# Power_Section.net
KiCad netlist of a schematic drawn in Altium Designer
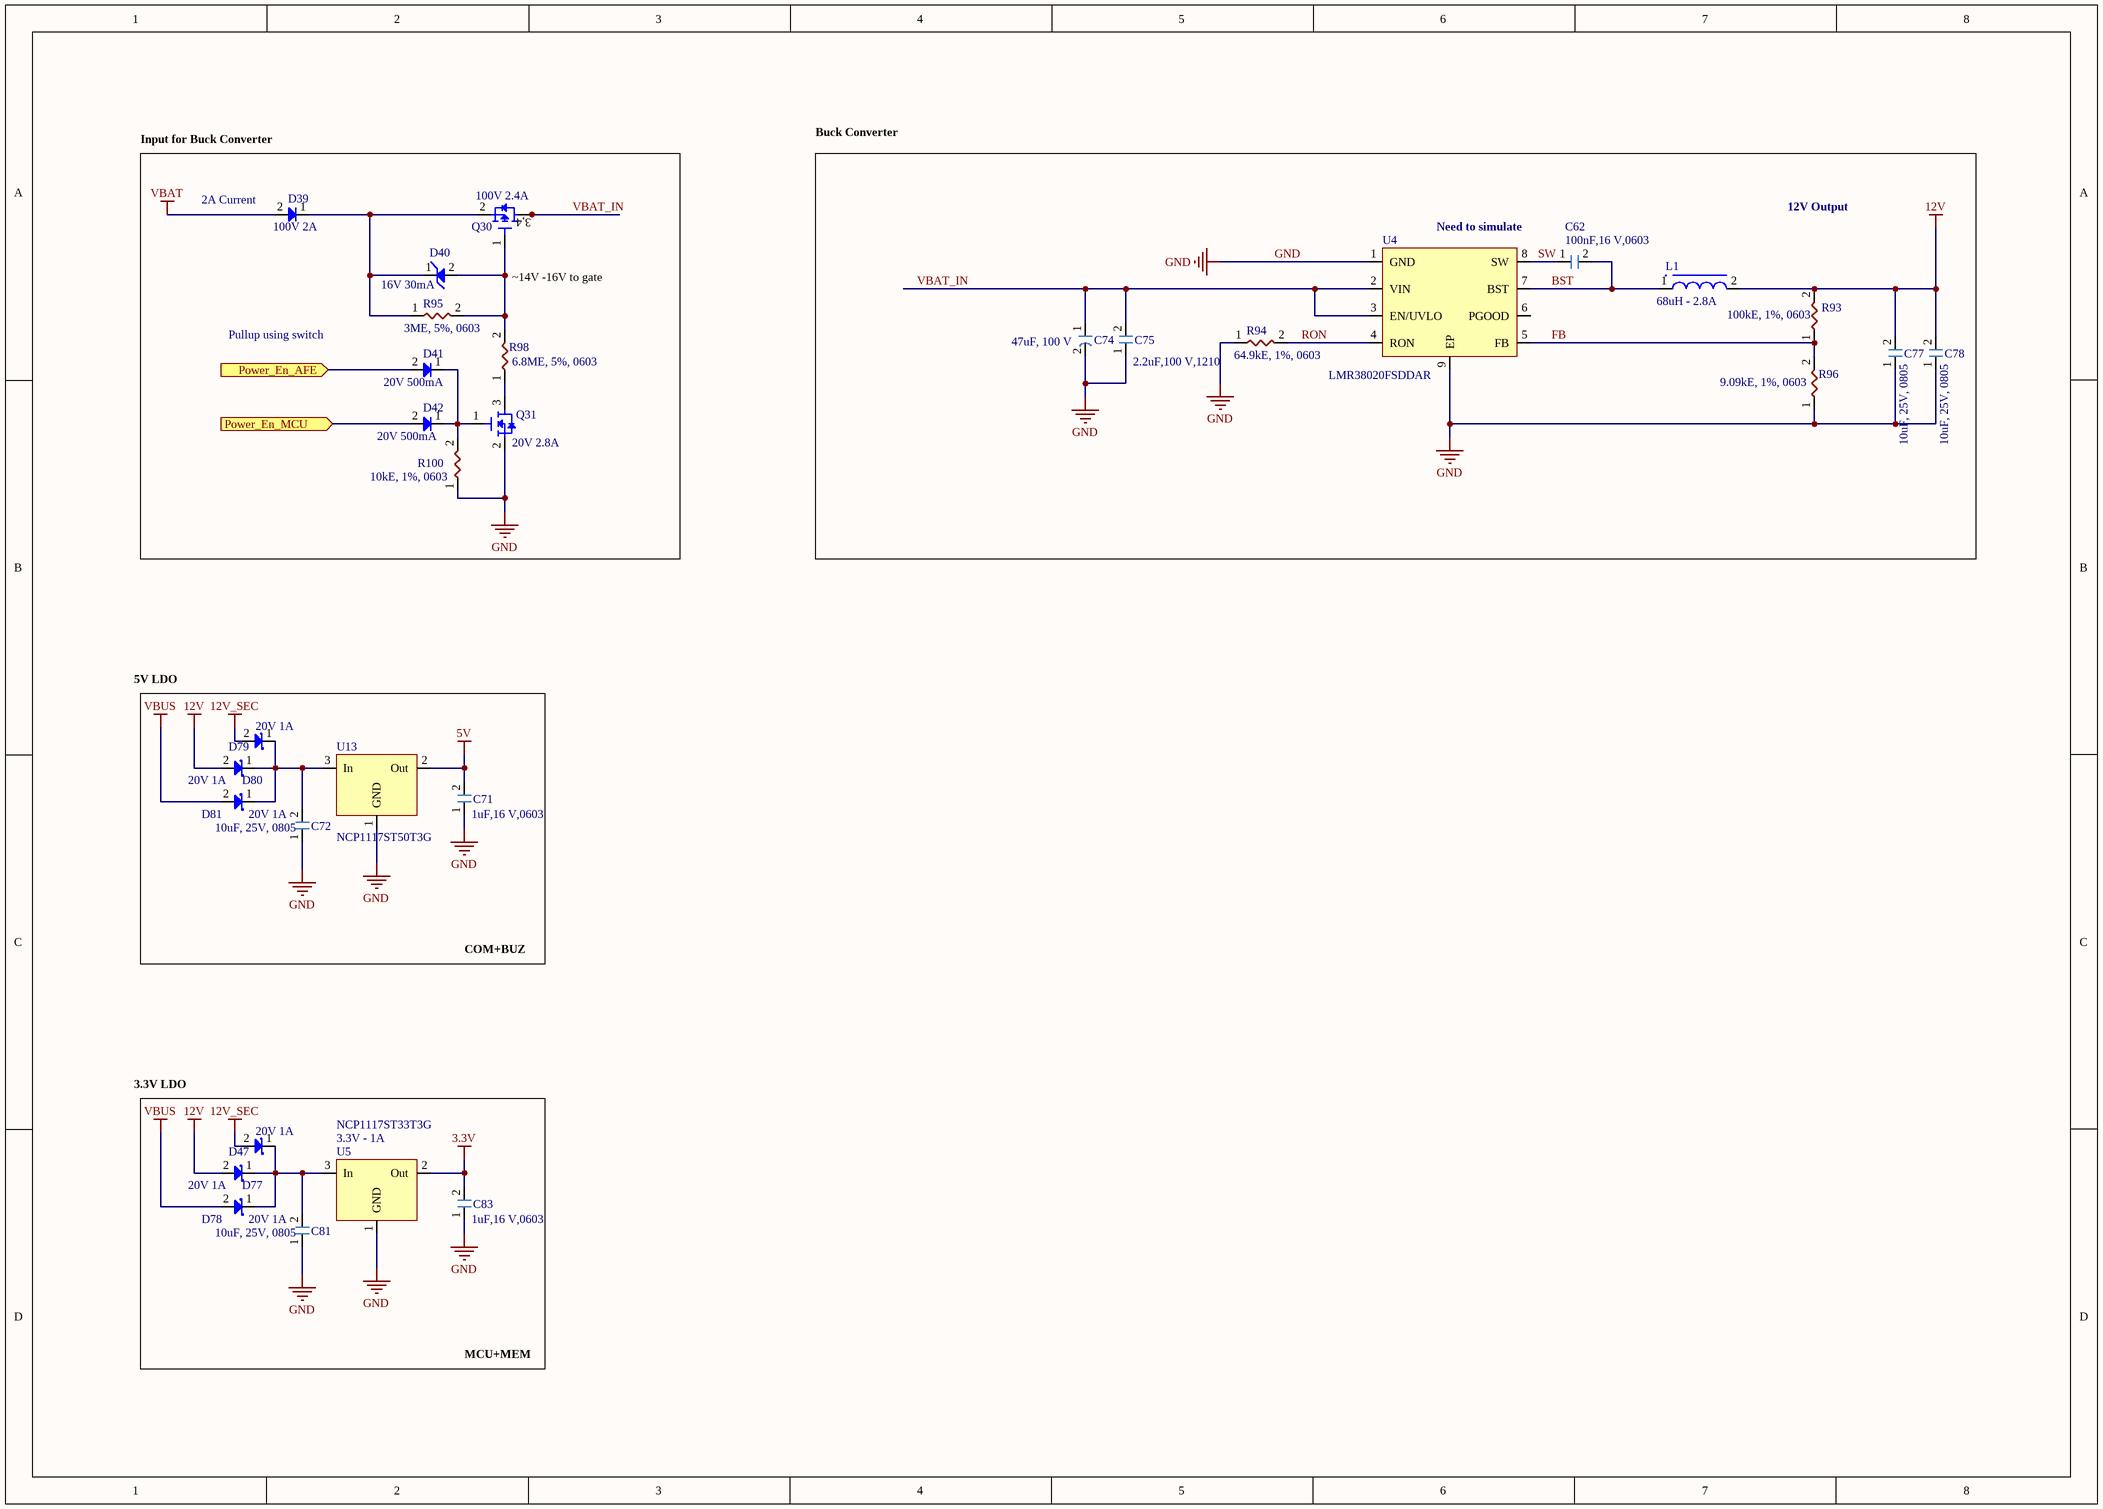
[diagram p0: Power Section.SchDoc]

(export (version "E")
  (design (tool "Eeschema 10.0.6"))
  (components
    (comp (ref "C62")
      (value "CC0603KRX7R7BB104")
      (footprint "BMS_V2.1_Adv:CAPC1608X05N 0603")
      (description "Multilayer Ceramic Capacitor, 100 nF, 16V, ±10%,  X7R 0603 [1608 Metric]")
      (fields
        (field (name "MANUFACTURER") "Yageo")
        (field (name "TOLERANCE") "10%")
        (field (name "VALUE DISPLAY") "100nF,16 V,0603")
      )
      (libsource (lib "BMS_V2.1_Adv") (part "Cap_CC0603KRX7R7BB104"))
    )
    (comp (ref "C71")
      (value "CGA3E1X7R1C105K080AC")
      (footprint "CAPC1608X05N 0603")
      (description "Multilayer Ceramic Capacitor, 1uF, 16V, ±10%,  X7R 0603 [1608 Metric]")
      (fields
        (field (name "MANUFACTURER") "TDK Corporation")
        (field (name "VOLTAGE") "16V")
        (field (name "VALUE DISPLAY") "1uF,16 V,0603")
      )
      (libsource (lib "BMS_V2.1_Adv") (part "Cap_CGA3E1X7R1C105K080AC"))
    )
    (comp (ref "C72")
      (value "GRM21BZ71E106KE15L")
      (footprint "BMS_V2.1_Adv:CAPC2012X13N 0805")
      (description "Multilayer Ceramic Capacitor, 10 uF, 25V, ±10%,  X7R 0805 (2012 Metric)")
      (fields
        (field (name "MANUFACTURER") "Murata")
        (field (name "TOLERANCE") "10%")
        (field (name "VALUE DISPLAY") "10uF, 25V, 0805")
      )
      (libsource (lib "BMS_V2.1_Adv") (part "Cap_GRM21BZ71E106KE15L"))
    )
    (comp (ref "C74")
      (value "ESW476M100AH2AA")
      (footprint "Aluminium Electrolytic Capacitor")
      (description "Aluminum Electrolytic Capacitors Radial, 47 µF 100 V, Can 370mOhm @ 100kHz 5000 Hrs @ 105°C")
      (fields
        (field (name "MANUFACTURER") "KEMET")
        (field (name "TOLERANCE") "20%")
        (field (name "VALUE DISPLAY") "47uF, 100 V")
      )
      (libsource (lib "BMS_V2.1_Adv") (part "Cap_ESW476M100AH2AA"))
    )
    (comp (ref "C75")
      (value "HMK325B7225KMHT")
      (footprint "CAPC3225X28N 1210")
      (description "Multilayer Ceramic Capacitor, 2.2 uF, 100 V, ± 10%, X7R, 1210 [3225 Metric]")
      (fields
        (field (name "MANUFACTURER") "Taiyo Yuden")
        (field (name "TOLERANCE") "10%")
        (field (name "VALUE DISPLAY") "2.2uF,100 V,1210")
      )
      (libsource (lib "BMS_V2.1_Adv") (part "Cap_HMK325B7225KMHT"))
    )
    (comp (ref "C77")
      (value "GRM21BZ71E106KE15L")
      (footprint "BMS_V2.1_Adv:CAPC2012X13N 0805")
      (description "Multilayer Ceramic Capacitor, 10 uF, 25V, ±10%,  X7R 0805 (2012 Metric)")
      (fields
        (field (name "MANUFACTURER") "Murata")
        (field (name "TOLERANCE") "10%")
        (field (name "VALUE DISPLAY") "10uF, 25V, 0805")
      )
      (libsource (lib "BMS_V2.1_Adv") (part "Cap_GRM21BZ71E106KE15L"))
    )
    (comp (ref "C78")
      (value "GRM21BZ71E106KE15L")
      (footprint "BMS_V2.1_Adv:CAPC2012X13N 0805")
      (description "Multilayer Ceramic Capacitor, 10 uF, 25V, ±10%,  X7R 0805 (2012 Metric)")
      (fields
        (field (name "MANUFACTURER") "Murata")
        (field (name "TOLERANCE") "10%")
        (field (name "VALUE DISPLAY") "10uF, 25V, 0805")
      )
      (libsource (lib "BMS_V2.1_Adv") (part "Cap_GRM21BZ71E106KE15L"))
    )
    (comp (ref "C81")
      (value "GRM21BZ71E106KE15L")
      (footprint "BMS_V2.1_Adv:CAPC2012X13N 0805")
      (description "Multilayer Ceramic Capacitor, 10 uF, 25V, ±10%,  X7R 0805 (2012 Metric)")
      (fields
        (field (name "MANUFACTURER") "Murata")
        (field (name "TOLERANCE") "10%")
        (field (name "VALUE DISPLAY") "10uF, 25V, 0805")
      )
      (libsource (lib "BMS_V2.1_Adv") (part "Cap_GRM21BZ71E106KE15L"))
    )
    (comp (ref "C83")
      (value "CGA3E1X7R1C105K080AC")
      (footprint "CAPC1608X05N 0603")
      (description "Multilayer Ceramic Capacitor, 1uF, 16V, ±10%,  X7R 0603 [1608 Metric]")
      (fields
        (field (name "MANUFACTURER") "TDK Corporation")
        (field (name "VOLTAGE") "16V")
        (field (name "VALUE DISPLAY") "1uF,16 V,0603")
      )
      (libsource (lib "BMS_V2.1_Adv") (part "Cap_CGA3E1X7R1C105K080AC"))
    )
    (comp (ref "D39")
      (value "STPS2H100ZFY")
      (footprint "SODFL350X110-2N")
      (description "Diode 100 V 2A Surface Mount SOD-123F")
      (fields
        (field (name "MANUFACTURER") "ST")
        (field (name "VALUE DISPLAY") "100V 2A")
        (field (name "VOLTAGE") "100V")
      )
      (libsource (lib "BMS_V2.1_Adv") (part "Diode_STPS2H100ZFY"))
    )
    (comp (ref "D40")
      (value "MMSZ5246BQ-7-F")
      (footprint "DIODE_SOD123")
      (description "Zener Diode 16 V 500 mW ±5% Surface Mount SOD-123")
      (fields
        (field (name "MANUFACTURER") "Diodes Inc.")
        (field (name "POWER") "370mW")
        (field (name "VALUE DISPLAY") "16V 30mA")
      )
      (libsource (lib "BMS_V2.1_Adv") (part "Diode_MMSZ5246BQ-7-F"))
    )
    (comp (ref "D41")
      (value "SBR80520LT1G")
      (footprint "DIODE_SOD123")
      (description "Diode 20 V 500mA Surface Mount SOD-123")
      (fields
        (field (name "MANUFACTURER") "OnSemi")
        (field (name "VALUE DISPLAY") "20V 500mA")
        (field (name "VOLTAGE") "20V")
      )
      (libsource (lib "BMS_V2.1_Adv") (part "Diode_SBR80520LT1G"))
    )
    (comp (ref "D42")
      (value "SBR80520LT1G")
      (footprint "DIODE_SOD123")
      (description "Diode 20 V 500mA Surface Mount SOD-123")
      (fields
        (field (name "MANUFACTURER") "OnSemi")
        (field (name "VALUE DISPLAY") "20V 500mA")
        (field (name "VOLTAGE") "20V")
      )
      (libsource (lib "BMS_V2.1_Adv") (part "Diode_SBR80520LT1G"))
    )
    (comp (ref "D47")
      (value "MBR120LSFT3G")
      (footprint "BMS_V2.1_Adv:SODFL360X98-2N")
      (description "DIODE SCHOTTKY 20V 1A SOD123FL")
      (fields
        (field (name "MANUFACTURER") "OnSemi")
        (field (name "VALUE DISPLAY") "20V 1A")
        (field (name "VOLTAGE") "20V")
      )
      (libsource (lib "BMS_V2.1_Adv") (part "Diode_MBR120LSFT3G"))
    )
    (comp (ref "D77")
      (value "MBR120LSFT3G")
      (footprint "BMS_V2.1_Adv:SODFL360X98-2N")
      (description "DIODE SCHOTTKY 20V 1A SOD123FL")
      (fields
        (field (name "MANUFACTURER") "OnSemi")
        (field (name "VALUE DISPLAY") "20V 1A")
        (field (name "VOLTAGE") "20V")
      )
      (libsource (lib "BMS_V2.1_Adv") (part "Diode_MBR120LSFT3G"))
    )
    (comp (ref "D78")
      (value "MBR120LSFT3G")
      (footprint "BMS_V2.1_Adv:SODFL360X98-2N")
      (description "DIODE SCHOTTKY 20V 1A SOD123FL")
      (fields
        (field (name "MANUFACTURER") "OnSemi")
        (field (name "VALUE DISPLAY") "20V 1A")
        (field (name "VOLTAGE") "20V")
      )
      (libsource (lib "BMS_V2.1_Adv") (part "Diode_MBR120LSFT3G"))
    )
    (comp (ref "D79")
      (value "MBR120LSFT3G")
      (footprint "BMS_V2.1_Adv:SODFL360X98-2N")
      (description "DIODE SCHOTTKY 20V 1A SOD123FL")
      (fields
        (field (name "MANUFACTURER") "OnSemi")
        (field (name "VALUE DISPLAY") "20V 1A")
        (field (name "VOLTAGE") "20V")
      )
      (libsource (lib "BMS_V2.1_Adv") (part "Diode_MBR120LSFT3G"))
    )
    (comp (ref "D80")
      (value "MBR120LSFT3G")
      (footprint "BMS_V2.1_Adv:SODFL360X98-2N")
      (description "DIODE SCHOTTKY 20V 1A SOD123FL")
      (fields
        (field (name "MANUFACTURER") "OnSemi")
        (field (name "VALUE DISPLAY") "20V 1A")
        (field (name "VOLTAGE") "20V")
      )
      (libsource (lib "BMS_V2.1_Adv") (part "Diode_MBR120LSFT3G"))
    )
    (comp (ref "D81")
      (value "MBR120LSFT3G")
      (footprint "BMS_V2.1_Adv:SODFL360X98-2N")
      (description "DIODE SCHOTTKY 20V 1A SOD123FL")
      (fields
        (field (name "MANUFACTURER") "OnSemi")
        (field (name "VALUE DISPLAY") "20V 1A")
        (field (name "VOLTAGE") "20V")
      )
      (libsource (lib "BMS_V2.1_Adv") (part "Diode_MBR120LSFT3G"))
    )
    (comp (ref "L1")
      (value "MSS1210-683ME")
      (footprint "BMS_V2.1_Adv:INDP120120X102N")
      (description "68 µH Shielded Drum Core, Wirewound Inductor 2.8 A 80mOhm Max Nonstandard")
      (fields
        (field (name "MANUFACTURER") "Coilcraft")
        (field (name "MANUFACTURER PART NUMBER") "MSS1210-683MED")
        (field (name "VALUE DISPLAY") "68uH - 2.8A")
      )
      (libsource (lib "BMS_V2.1_Adv") (part "Ind_MSS1210-683ME"))
    )
    (comp (ref "Q30")
      (value "ZXMP10A17GQTA")
      (footprint "SOT230P700X180-4N")
      (description "P-Channel 100 V 2.4A (Ta) 2W (Ta) Surface Mount SOT-223-3")
      (fields
        (field (name "MANUFACTURER") "Diodes Inc.")
        (field (name "POWER") "2W")
        (field (name "VALUE DISPLAY") "100V 2.4A")
      )
      (libsource (lib "BMS_V2.1_Adv") (part "FET_ZXMP10A17GQTA"))
    )
    (comp (ref "Q31")
      (value "DMG2302UK-7")
      (footprint "BMS_V2.1_Adv:SOT95P255X140-3N")
      (description "N-Channel 20 V 2.8A (Ta) 660mW (Ta) Surface Mount SOT-23-3")
      (fields
        (field (name "MANUFACTURER") "Diodes Inc.")
        (field (name "POWER") "660mW")
        (field (name "VALUE DISPLAY") "20V 2.8A")
      )
      (libsource (lib "BMS_V2.1_Adv") (part "FET_DMG2302UK-7"))
    )
    (comp (ref "R93")
      (value "CRCW0805100KFKEA")
      (footprint "BMS_V2.1_Adv:RESC1608X05N 0603")
      (description "SMD Chip Resistor, 100k Ohm, ± 1%, 100 mW, 0603 [1608 Metric], Thick Film, General Purpose")
      (fields
        (field (name "MANUFACTURER") "Vishay Dale")
        (field (name "MANUFACTURER PART NUMBER") "CRCW0603100KFKEA")
        (field (name "VALUE DISPLAY") "100kE, 1%, 0603")
      )
      (libsource (lib "BMS_V2.1_Adv") (part "Res_CRCW0603100KFKEA"))
    )
    (comp (ref "R94")
      (value "AC0603FR-0764K9L")
      (footprint "BMS_V2.1_Adv:RESC1608X05N 0603")
      (fields
        (field (name "MANUFACTURER") "Yageo")
        (field (name "POWER") "1/10W")
        (field (name "TOLERANCE") "1%")
        (field (name "VALUE DISPLAY") "64.9kE, 1%, 0603")
      )
      (libsource (lib "BMS_V2.1_Adv") (part "Res_AC0603FR-0764K9L"))
    )
    (comp (ref "R95")
      (value "CRCW06033M00JNEA")
      (footprint "RESC1608X05N 0603")
      (fields
        (field (name "MANUFACTURER") "Vishay Dale")
        (field (name "POWER") "1/10W")
        (field (name "TOLERANCE") "5%")
        (field (name "VALUE DISPLAY") "3ME, 5%, 0603")
      )
      (libsource (lib "BMS_V2.1_Adv") (part "Res_CRCW06033M00JNEA"))
    )
    (comp (ref "R96")
      (value "AC0603FR-079K09L")
      (footprint "BMS_V2.1_Adv:RESC1608X05N 0603")
      (fields
        (field (name "MANUFACTURER") "Yageo")
        (field (name "POWER") "1/10W")
        (field (name "TOLERANCE") "1%")
        (field (name "VALUE DISPLAY") "9.09kE, 1%, 0603")
      )
      (libsource (lib "BMS_V2.1_Adv") (part "Res_AC0603FR-079K09L"))
    )
    (comp (ref "R98")
      (value "CRCW06036M80JNEA")
      (footprint "RESC1608X05N 0603")
      (fields
        (field (name "MANUFACTURER") "Vishay Dale")
        (field (name "POWER") "1/10W")
        (field (name "TOLERANCE") "5%")
        (field (name "VALUE DISPLAY") "6.8ME, 5%, 0603")
      )
      (libsource (lib "BMS_V2.1_Adv") (part "Res_CRCW06036M80JNEA"))
    )
    (comp (ref "R100")
      (value "CRCW060310K0FKEA")
      (footprint "RESC1608X05N 0603")
      (description "SMD Chip Resistor, 10 kOhm,±1%, 100 mW, 0603 [1608 Metric], Thick Film, General Purpose")
      (fields
        (field (name "MANUFACTURER") "Vishay Dale")
        (field (name "POWER") "1/10W")
        (field (name "VALUE DISPLAY") "10kE, 1%, 0603")
      )
      (libsource (lib "BMS_V2.1_Adv") (part "Res_CRCW060310K0FKEA"))
    )
    (comp (ref "U4")
      (value "LMR38020FSDDAR")
      (footprint "BMS_V2.1_Adv:SOIC127P600X170_HS-9N LM5164")
      (description "Buck Switching Regulator IC Positive Adjustable 1V 1 Output 2A 8-PowerSOIC (0.154\", 3.90mm Width)")
      (fields (field (name "MANUFACTURER") "Texas Instruments") (field (name "VOLTAGE") "4.5V - 80V"))
      (libsource (lib "BMS_V2.1_Adv") (part "IC_LMR38020FSDDAR"))
    )
    (comp (ref "U5")
      (value "NCP1117ST33T3G")
      (footprint "BMS_V2.1_Adv:SOT230P700X180-4N - NCP")
      (description "LDO Voltage Regulators 3.3V 1A Positive")
      (fields
        (field (name "MANUFACTURER") "OnSemi")
        (field (name "VALUE DISPLAY") "3.3V - 1A")
        (field (name "VOLTAGE") "20V (Max)")
      )
      (libsource (lib "BMS_V2.1_Adv") (part "IC_NCP1117ST33T3G"))
    )
    (comp (ref "U13")
      (value "NCP1117ST50T3G")
      (footprint "BMS_V2.1_Adv:SOT230P700X180-4N - NCP")
      (description "LDO Voltage Regulators 5V 1A Positive")
      (fields (field (name "MANUFACTURER") "OnSemi") (field (name "VOLTAGE") "20V (Max)"))
      (libsource (lib "BMS_V2.1_Adv") (part "IC_NCP1117ST50T3G"))
    )
  )
  (nets
    (net (code "1") (name "/BST") (class "Default")
      (node (ref "C62") (pin "2") (pinfunction "2_2") (pintype "passive"))
      (node (ref "L1") (pin "1") (pinfunction "1_1") (pintype "passive"))
      (node (ref "U4") (pin "7") (pinfunction "BST_7") (pintype "passive"))
    )
    (net (code "2") (name "/FB") (class "Default")
      (node (ref "R93") (pin "1") (pinfunction "1_1") (pintype "passive"))
      (node (ref "R96") (pin "2") (pinfunction "2_2") (pintype "passive"))
      (node (ref "U4") (pin "5") (pinfunction "FB_5") (pintype "passive"))
    )
    (net (code "3") (name "/Power_En_AFE") (class "Default")
      (node (ref "D41") (pin "2") (pinfunction "Anode_2") (pintype "passive"))
    )
    (net (code "4") (name "/Power_En_MCU") (class "Default")
      (node (ref "D42") (pin "2") (pinfunction "Anode_2") (pintype "passive"))
    )
    (net (code "5") (name "/RON") (class "Default")
      (node (ref "R94") (pin "2") (pinfunction "2_2") (pintype "passive"))
      (node (ref "U4") (pin "4") (pinfunction "RON_4") (pintype "passive"))
    )
    (net (code "6") (name "/SW") (class "Default")
      (node (ref "C62") (pin "1") (pinfunction "1_1") (pintype "passive"))
      (node (ref "U4") (pin "8") (pinfunction "SW_8") (pintype "passive"))
    )
    (net (code "7") (name "/VBAT_IN") (class "Default")
      (node (ref "C74") (pin "1") (pinfunction "1_1") (pintype "passive"))
      (node (ref "C75") (pin "2") (pinfunction "2_2") (pintype "passive"))
      (node (ref "Q30") (pin "3") (pinfunction "Drain_3") (pintype "passive"))
      (node (ref "Q30") (pin "4") (pinfunction "Drain_4") (pintype "passive"))
      (node (ref "U4") (pin "2") (pinfunction "VIN_2") (pintype "passive"))
      (node (ref "U4") (pin "3") (pinfunction "EN/UVLO_3") (pintype "passive"))
    )
    (net (code "8") (name "3.3V") (class "Default")
      (node (ref "C83") (pin "2") (pinfunction "2_2") (pintype "passive"))
      (node (ref "U5") (pin "2") (pinfunction "Out_2") (pintype "passive"))
    )
    (net (code "9") (name "5V") (class "Default")
      (node (ref "C71") (pin "2") (pinfunction "2_2") (pintype "passive"))
      (node (ref "U13") (pin "2") (pinfunction "Out_2") (pintype "passive"))
    )
    (net (code "10") (name "12V") (class "Default")
      (node (ref "C77") (pin "2") (pinfunction "2_2") (pintype "passive"))
      (node (ref "C78") (pin "2") (pinfunction "2_2") (pintype "passive"))
      (node (ref "D77") (pin "2") (pinfunction "Anode_2") (pintype "passive"))
      (node (ref "D80") (pin "2") (pinfunction "Anode_2") (pintype "passive"))
      (node (ref "L1") (pin "2") (pinfunction "2_2") (pintype "passive"))
      (node (ref "R93") (pin "2") (pinfunction "2_2") (pintype "passive"))
    )
    (net (code "11") (name "12V_SEC") (class "Default")
      (node (ref "D47") (pin "2") (pinfunction "Anode_2") (pintype "passive"))
      (node (ref "D79") (pin "2") (pinfunction "Anode_2") (pintype "passive"))
    )
    (net (code "12") (name "GND") (class "Default")
      (node (ref "C71") (pin "1") (pinfunction "1_1") (pintype "passive"))
      (node (ref "C72") (pin "1") (pinfunction "1_1") (pintype "passive"))
      (node (ref "C74") (pin "2") (pinfunction "2_2") (pintype "passive"))
      (node (ref "C75") (pin "1") (pinfunction "1_1") (pintype "passive"))
      (node (ref "C77") (pin "1") (pinfunction "1_1") (pintype "passive"))
      (node (ref "C78") (pin "1") (pinfunction "1_1") (pintype "passive"))
      (node (ref "C81") (pin "1") (pinfunction "1_1") (pintype "passive"))
      (node (ref "C83") (pin "1") (pinfunction "1_1") (pintype "passive"))
      (node (ref "Q31") (pin "2") (pinfunction "Source_2") (pintype "passive"))
      (node (ref "R100") (pin "1") (pinfunction "1_1") (pintype "passive"))
      (node (ref "R94") (pin "1") (pinfunction "1_1") (pintype "passive"))
      (node (ref "R96") (pin "1") (pinfunction "1_1") (pintype "passive"))
      (node (ref "U13") (pin "1") (pinfunction "GND_1") (pintype "passive"))
      (node (ref "U4") (pin "1") (pinfunction "GND_1") (pintype "passive"))
      (node (ref "U4") (pin "9") (pinfunction "EP_9") (pintype "passive"))
      (node (ref "U5") (pin "1") (pinfunction "GND_1") (pintype "passive"))
    )
    (net (code "13") (name "Net-(D39-Cathode)") (class "Default")
      (node (ref "D39") (pin "1") (pinfunction "Cathode_1") (pintype "passive"))
      (node (ref "D40") (pin "1") (pinfunction "Cathode_1") (pintype "passive"))
      (node (ref "Q30") (pin "2") (pinfunction "Source_2") (pintype "passive"))
      (node (ref "R95") (pin "1") (pinfunction "1_1") (pintype "passive"))
    )
    (net (code "14") (name "Net-(D40-Anode)") (class "Default")
      (node (ref "D40") (pin "2") (pinfunction "Anode_2") (pintype "passive"))
      (node (ref "Q30") (pin "1") (pinfunction "Gate_1") (pintype "passive"))
      (node (ref "R95") (pin "2") (pinfunction "2_2") (pintype "passive"))
      (node (ref "R98") (pin "2") (pinfunction "2_2") (pintype "passive"))
    )
    (net (code "15") (name "Net-(D41-Cathode)") (class "Default")
      (node (ref "D41") (pin "1") (pinfunction "Cathode_1") (pintype "passive"))
      (node (ref "D42") (pin "1") (pinfunction "Cathode_1") (pintype "passive"))
      (node (ref "Q31") (pin "1") (pinfunction "Gate_1") (pintype "passive"))
      (node (ref "R100") (pin "2") (pinfunction "2_2") (pintype "passive"))
    )
    (net (code "16") (name "Net-(D47-Cathode)") (class "Default")
      (node (ref "C81") (pin "2") (pinfunction "2_2") (pintype "passive"))
      (node (ref "D47") (pin "1") (pinfunction "Cathode_1") (pintype "passive"))
      (node (ref "D77") (pin "1") (pinfunction "Cathode_1") (pintype "passive"))
      (node (ref "D78") (pin "1") (pinfunction "Cathode_1") (pintype "passive"))
      (node (ref "U5") (pin "3") (pinfunction "In_3") (pintype "passive"))
    )
    (net (code "17") (name "Net-(D79-Cathode)") (class "Default")
      (node (ref "C72") (pin "2") (pinfunction "2_2") (pintype "passive"))
      (node (ref "D79") (pin "1") (pinfunction "Cathode_1") (pintype "passive"))
      (node (ref "D80") (pin "1") (pinfunction "Cathode_1") (pintype "passive"))
      (node (ref "D81") (pin "1") (pinfunction "Cathode_1") (pintype "passive"))
      (node (ref "U13") (pin "3") (pinfunction "In_3") (pintype "passive"))
    )
    (net (code "18") (name "Net-(Q31-Drain)") (class "Default")
      (node (ref "Q31") (pin "3") (pinfunction "Drain_3") (pintype "passive"))
      (node (ref "R98") (pin "1") (pinfunction "1_1") (pintype "passive"))
    )
    (net (code "19") (name "VBAT") (class "Default")
      (node (ref "D39") (pin "2") (pinfunction "Anode_2") (pintype "passive"))
    )
    (net (code "20") (name "VBUS") (class "Default")
      (node (ref "D78") (pin "2") (pinfunction "Anode_2") (pintype "passive"))
      (node (ref "D81") (pin "2") (pinfunction "Anode_2") (pintype "passive"))
    )
    (net (code "21") (name "unconnected-(U4-PGOOD-Pad6)") (class "Default")
      (node (ref "U4") (pin "6") (pinfunction "PGOOD_6") (pintype "passive"))
    )
  )
)
